# MotorDriver-rev1.net
KiCad netlist of a schematic drawn in EAGLE
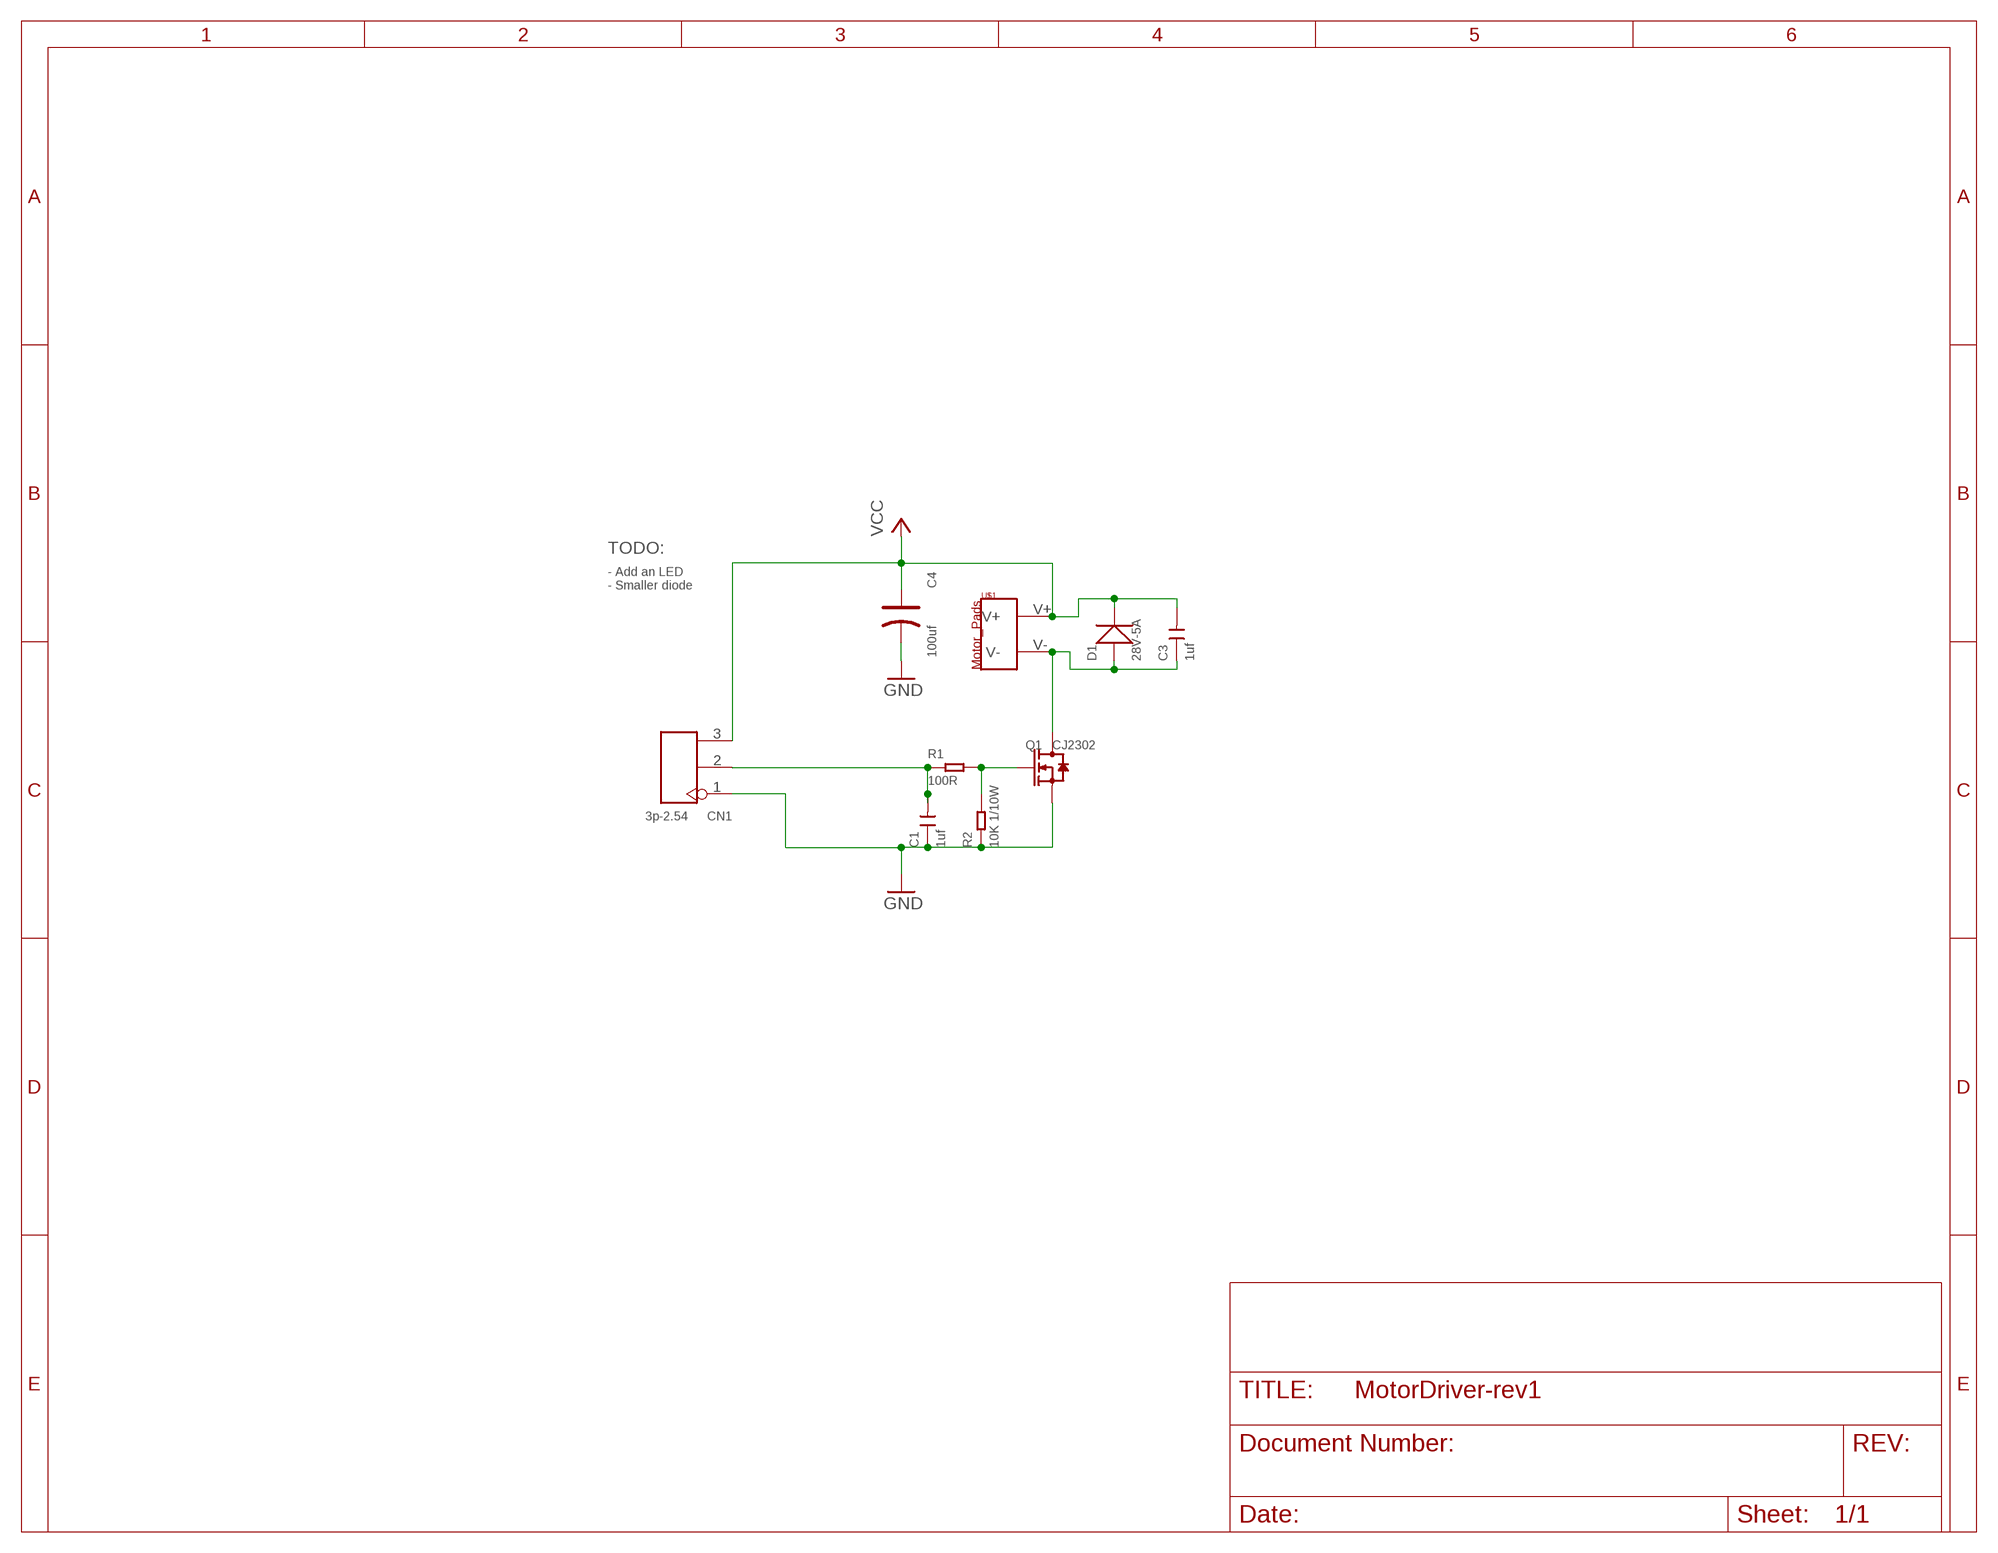
[diagram p0: schematic, sheet 1]

(export (version "E")
  (design (tool "Eeschema 10.0.6"))
  (components
    (comp (ref "C1")
      (value "1uf")
      (footprint "eagle-import:C0402")
      (fields (field (name "MPN") "CC0402KRX5R6BB105"))
      (libsource (lib "eagle-import") (part "CERAMIC-1UF-10V-10%-X5R(0402)"))
    )
    (comp (ref "C3")
      (value "1uf")
      (footprint "eagle-import:C0603")
      (fields (field (name "MPN") "CC0603KRX7R8BB105"))
      (libsource (lib "eagle-import") (part "CERAMIC-1UF-25V-10%-X7R(0603)"))
    )
    (comp (ref "C4")
      (value "100uf")
      (footprint "eagle-import:AVX-B")
      (fields (field (name "MPN") "TAJB107M010#NJ"))
      (libsource (lib "eagle-import") (part "TANTALUM-SMD-100UF-10V(AVX-B)"))
    )
    (comp (ref "CN1")
      (value "3p-2.54")
      (footprint "eagle-import:H3-2.54")
      (libsource (lib "eagle-import") (part "DIP-BLACK-MALE-HEADER-VERT(3P-2.54)"))
    )
    (comp (ref "D1")
      (value "28V-5A")
      (footprint "eagle-import:DO-214AA")
      (fields (field (name "MPN") "SS54B"))
      (libsource (lib "eagle-import") (part "SMD-DIODE-SCHOTTKY-28V-5A(DO-214AA)"))
    )
    (comp (ref "Q1")
      (value "CJ2302")
      (footprint "eagle-import:SOT-23")
      (libsource (lib "eagle-import") (part "SMD-MOSFET-N-CH-20V-2.1A-CJ2302(SOT-23)"))
    )
    (comp (ref "R1")
      (value "100R")
      (footprint "eagle-import:R0603")
      (fields (field (name "MPN") "RC0603JR-07100RL"))
      (libsource (lib "eagle-import") (part "SMD-RES-100R-5%-1/10W(0603)"))
    )
    (comp (ref "R2")
      (value "10K 1/10W")
      (footprint "eagle-import:R0603")
      (fields (field (name "MPN") "RC0603JR-0710KL"))
      (libsource (lib "eagle-import") (part "SMD-RES-10K-5%-1/10W(0603)"))
    )
    (comp (ref "U$1")
      (value "MOTOR_PADS")
      (footprint "eagle-import:MOTOR_PADS")
      (libsource (lib "eagle-import") (part "MOTOR_PADS"))
    )
  )
  (nets
    (net (code "1") (name "GND") (class "Default")
      (node (ref "C1") (pin "1") (pinfunction "1_1") (pintype "passive"))
      (node (ref "C4") (pin "-") (pinfunction "-_-") (pintype "passive"))
      (node (ref "CN1") (pin "1") (pinfunction "P$1_1") (pintype "bidirectional"))
      (node (ref "Q1") (pin "2") (pinfunction "S_2") (pintype "passive"))
      (node (ref "R2") (pin "1") (pinfunction "1_1") (pintype "passive"))
    )
    (net (code "2") (name "Net-(CN1-P$2)") (class "Default")
      (node (ref "C1") (pin "2") (pinfunction "2_2") (pintype "passive"))
      (node (ref "CN1") (pin "2") (pinfunction "P$2_2") (pintype "bidirectional"))
      (node (ref "R1") (pin "1") (pinfunction "1_1") (pintype "passive"))
    )
    (net (code "3") (name "Net-(Q1-D)") (class "Default")
      (node (ref "C3") (pin "1") (pinfunction "1_1") (pintype "passive"))
      (node (ref "D1") (pin "+") (pinfunction "+_+") (pintype "passive"))
      (node (ref "Q1") (pin "3") (pinfunction "D_3") (pintype "passive"))
      (node (ref "U$1") (pin "V-") (pinfunction "V-_V-") (pintype "bidirectional"))
    )
    (net (code "4") (name "Net-(Q1-G)") (class "Default")
      (node (ref "Q1") (pin "1") (pinfunction "G_1") (pintype "passive"))
      (node (ref "R1") (pin "2") (pinfunction "2_2") (pintype "passive"))
      (node (ref "R2") (pin "2") (pinfunction "2_2") (pintype "passive"))
    )
    (net (code "5") (name "VCC") (class "Default")
      (node (ref "C3") (pin "2") (pinfunction "2_2") (pintype "passive"))
      (node (ref "C4") (pin "+") (pinfunction "+_+") (pintype "passive"))
      (node (ref "CN1") (pin "3") (pinfunction "P$3_3") (pintype "bidirectional"))
      (node (ref "D1") (pin "-") (pinfunction "-_-") (pintype "passive"))
      (node (ref "U$1") (pin "V+") (pinfunction "V+_V+") (pintype "bidirectional"))
    )
  )
)
